# 12V_to_3V3.net
KiCad netlist of a schematic drawn in Altium Designer
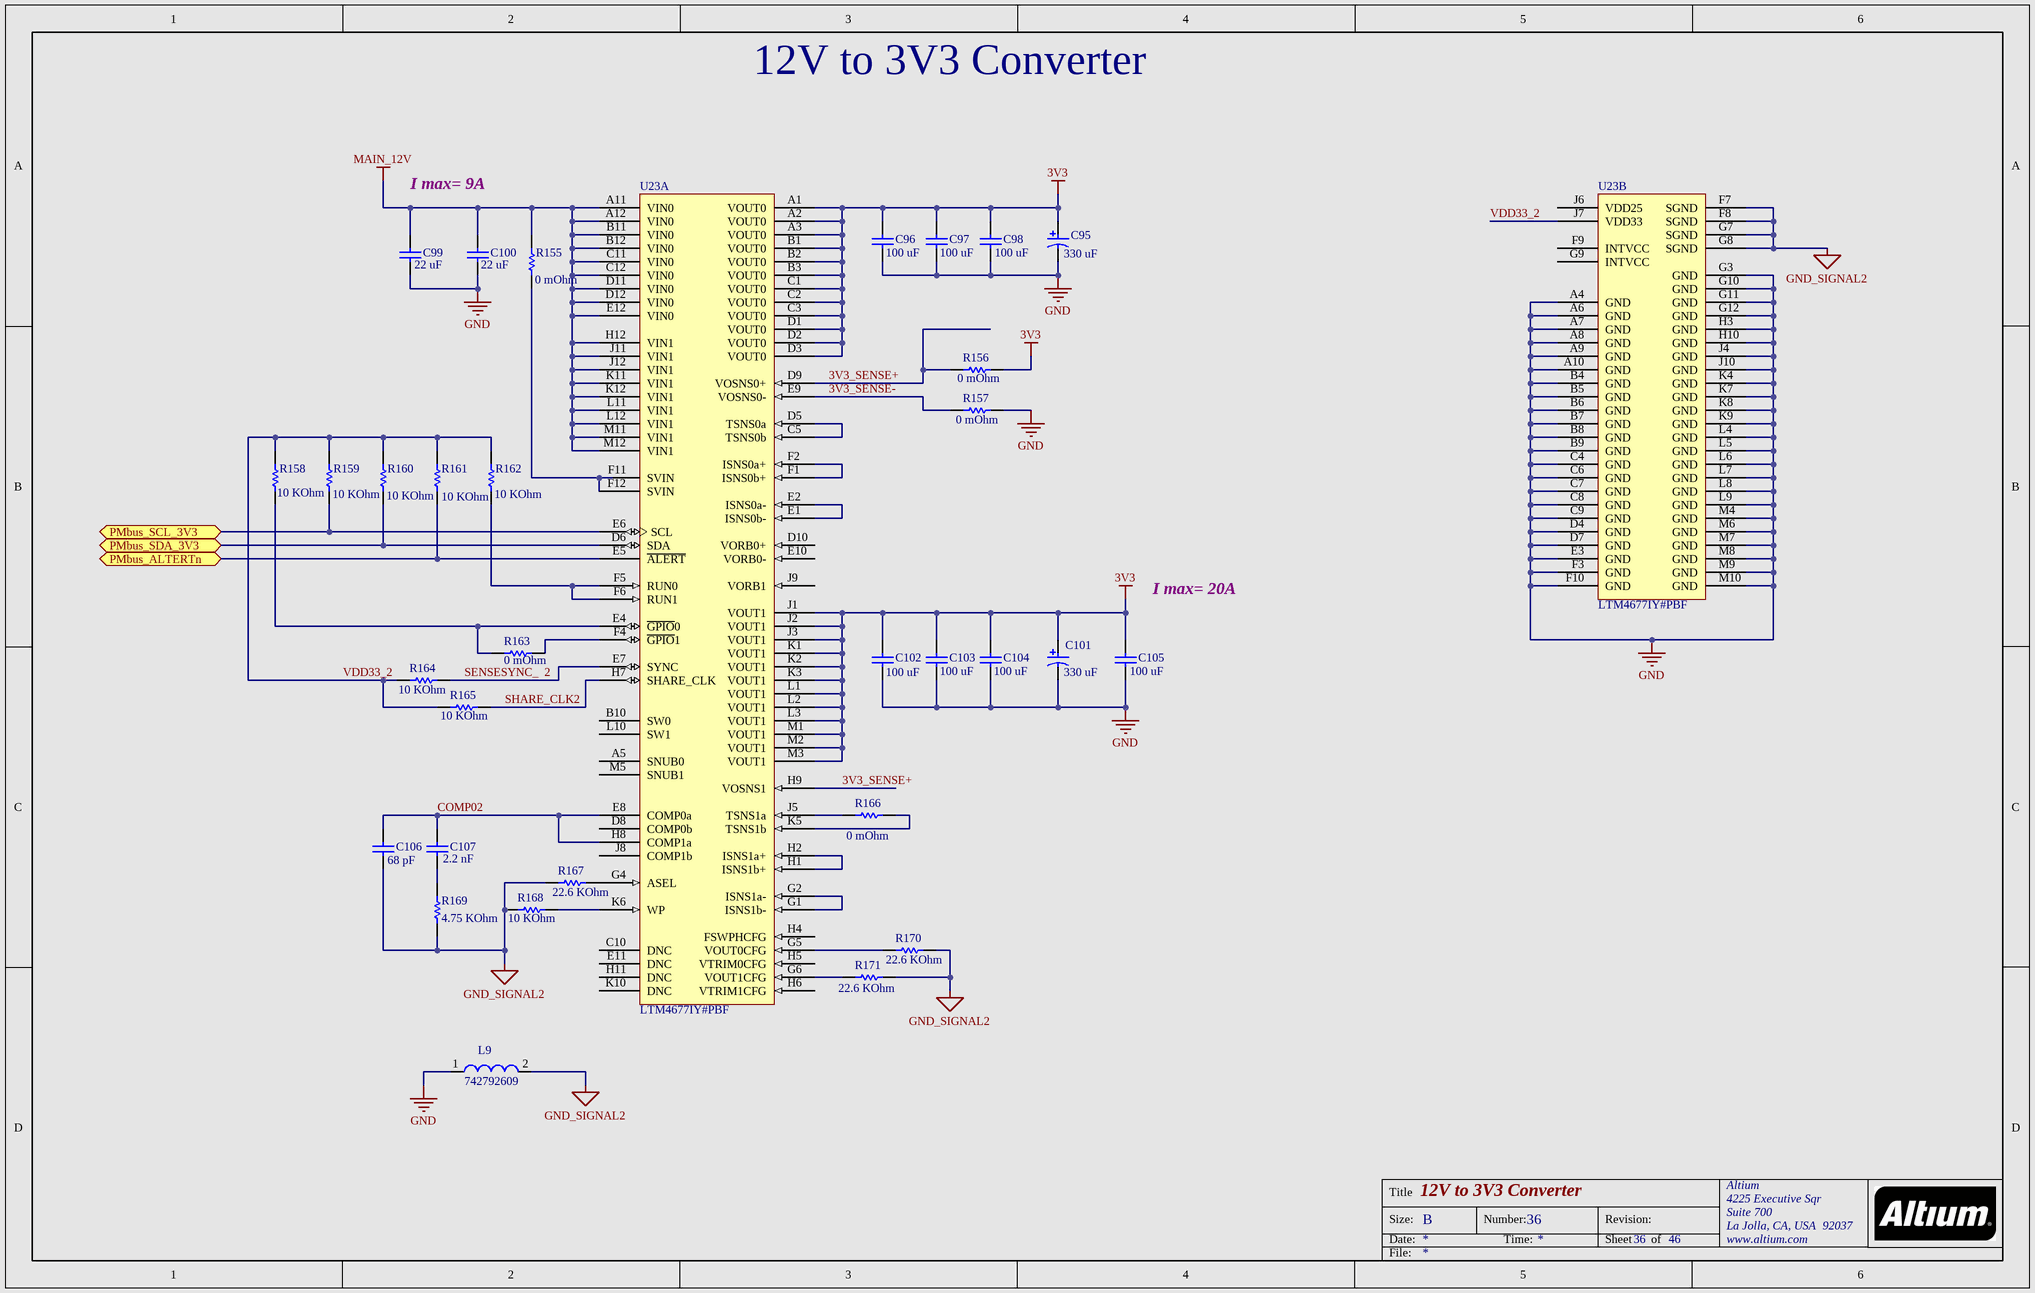
[diagram p0: 12V_to_3V3.SchDoc]

(export (version "E")
  (design (tool "Eeschema 10.0.6"))
  (components
    (comp (ref "C95")
      (value "6TPF330M9L")
      (footprint "PNSC-TPF-D3L_V")
      (description "Tantalum Capacitor, 330 uF, +/- 20%, 6.3 V, -55 to 105 degC, 2-Pin Molded, RoHS, Tape and Reel")
      (fields (field (name "CAPACITANCE") "330 uF"))
      (libsource (lib "Altium Content Vault") (part "CMP-1665-00019-2"))
    )
    (comp (ref "C96")
      (value "GRM31CR60J107ME39L")
      (footprint "CAPC3216X190X55ML30T25")
      (description "Chip Capacitor, 100 uF, +/- 20%, 6.3 V, -55 to 85 degC, 1206 (3216 Metric), RoHS, Tape and Reel")
      (fields (field (name "TOLERANCE") "20%") (field (name "CAPACITANCE") "100 uF"))
      (libsource (lib "Altium Content Vault") (part "CAP-NP-2"))
    )
    (comp (ref "C97")
      (value "GRM31CR60J107ME39L")
      (footprint "CAPC3216X190X55ML30T25")
      (description "Chip Capacitor, 100 uF, +/- 20%, 6.3 V, -55 to 85 degC, 1206 (3216 Metric), RoHS, Tape and Reel")
      (fields (field (name "TOLERANCE") "20%") (field (name "CAPACITANCE") "100 uF"))
      (libsource (lib "Altium Content Vault") (part "CAP-NP-2"))
    )
    (comp (ref "C98")
      (value "GRM31CR60J107ME39L")
      (footprint "CAPC3216X190X55ML30T25")
      (description "Chip Capacitor, 100 uF, +/- 20%, 6.3 V, -55 to 85 degC, 1206 (3216 Metric), RoHS, Tape and Reel")
      (fields (field (name "TOLERANCE") "20%") (field (name "CAPACITANCE") "100 uF"))
      (libsource (lib "Altium Content Vault") (part "CAP-NP-2"))
    )
    (comp (ref "C99")
      (value "GRM31CR61E226KE15L")
      (footprint "CAPC3216X180X55ML20T25")
      (description "Chip Capacitor, 22 uF, +/- 10%, 25 V, -55 to 85 degC, 1206 (3216 Metric), RoHS, Tape and Reel")
      (fields (field (name "TOLERANCE") "10%") (field (name "CAPACITANCE") "22 uF"))
      (libsource (lib "Altium Content Vault") (part "CAP-NP-2"))
    )
    (comp (ref "C100")
      (value "GRM31CR61E226KE15L")
      (footprint "CAPC3216X180X55ML20T25")
      (description "Chip Capacitor, 22 uF, +/- 10%, 25 V, -55 to 85 degC, 1206 (3216 Metric), RoHS, Tape and Reel")
      (fields (field (name "TOLERANCE") "10%") (field (name "CAPACITANCE") "22 uF"))
      (libsource (lib "Altium Content Vault") (part "CAP-NP-2"))
    )
    (comp (ref "C101")
      (value "6TPF330M9L")
      (footprint "PNSC-TPF-D3L_V")
      (description "Tantalum Capacitor, 330 uF, +/- 20%, 6.3 V, -55 to 105 degC, 2-Pin Molded, RoHS, Tape and Reel")
      (fields (field (name "CAPACITANCE") "330 uF"))
      (libsource (lib "Altium Content Vault") (part "CMP-1665-00019-2"))
    )
    (comp (ref "C102")
      (value "GRM31CR60J107ME39L")
      (footprint "CAPC3216X190X55ML30T25")
      (description "Chip Capacitor, 100 uF, +/- 20%, 6.3 V, -55 to 85 degC, 1206 (3216 Metric), RoHS, Tape and Reel")
      (fields (field (name "TOLERANCE") "20%") (field (name "CAPACITANCE") "100 uF"))
      (libsource (lib "Altium Content Vault") (part "CAP-NP-2"))
    )
    (comp (ref "C103")
      (value "GRM31CR60J107ME39L")
      (footprint "CAPC3216X190X55ML30T25")
      (description "Chip Capacitor, 100 uF, +/- 20%, 6.3 V, -55 to 85 degC, 1206 (3216 Metric), RoHS, Tape and Reel")
      (fields (field (name "TOLERANCE") "20%") (field (name "CAPACITANCE") "100 uF"))
      (libsource (lib "Altium Content Vault") (part "CAP-NP-2"))
    )
    (comp (ref "C104")
      (value "GRM31CR60J107ME39L")
      (footprint "CAPC3216X190X55ML30T25")
      (description "Chip Capacitor, 100 uF, +/- 20%, 6.3 V, -55 to 85 degC, 1206 (3216 Metric), RoHS, Tape and Reel")
      (fields (field (name "TOLERANCE") "20%") (field (name "CAPACITANCE") "100 uF"))
      (libsource (lib "Altium Content Vault") (part "CAP-NP-2"))
    )
    (comp (ref "C105")
      (value "GRM31CR60J107ME39L")
      (footprint "CAPC3216X190X55ML30T25")
      (description "Chip Capacitor, 100 uF, +/- 20%, 6.3 V, -55 to 85 degC, 1206 (3216 Metric), RoHS, Tape and Reel")
      (fields (field (name "TOLERANCE") "20%") (field (name "CAPACITANCE") "100 uF"))
      (libsource (lib "Altium Content Vault") (part "CAP-NP-2"))
    )
    (comp (ref "C106")
      (value "ECJ-0EC1H680J")
      (footprint "CAPC1005X55X20ML5T10")
      (description "Chip Capacitor, 68 pF, +/- 5%, 50 V, -55 to 125 degC, 0402 (1005 Metric), RoHS, Tape and Reel")
      (fields (field (name "TOLERANCE") "5%") (field (name "CAPACITANCE") "68 pF"))
      (libsource (lib "Altium Content Vault") (part "CMP-1665-00023-1"))
    )
    (comp (ref "C107")
      (value "CGJ2B2X7R1E222K050BA")
      (footprint "CAPC1005X55X10ML05")
      (description "Chip Capacitor, 2.2 nF, +/- 10%, 25 V, -55 to 125 degC, 0402 (1005 Metric), RoHS, Tape and Reel")
      (fields (field (name "TOLERANCE") "10%") (field (name "CAPACITANCE") "2.2 nF"))
      (libsource (lib "Altium Content Vault") (part "CAP-NP-2"))
    )
    (comp (ref "L9")
      (value "742792609")
      (footprint "SMD-0603")
      (description "SMD EMI Suppression Ferrite Bead WE-CBF, Z = 30 Ohm")
      (libsource (lib "Altium Content Vault") (part "CMP-0220-00193-1"))
    )
    (comp (ref "R155")
      (value "ERJ-2GE0R00X")
      (footprint "RESC1005X40X25ML05T05")
      (description "Chip Resistor, 0 mOhm, +/- 5%, 100 mW, -55 to 155 degC, 0402 (1005 Metric), RoHS, Tape and Reel")
      (fields
        (field (name "TOLERANCE") "5%")
        (field (name "RESISTANCE") "0 mOhm")
        (field (name "MANUFACTURER") "Basic Passives")
      )
      (libsource (lib "Altium Content Vault") (part "RES-2"))
    )
    (comp (ref "R156")
      (value "ERJ-2GE0R00X")
      (footprint "RESC1005X40X25ML05T05")
      (description "Chip Resistor, 0 mOhm, +/- 5%, 100 mW, -55 to 155 degC, 0402 (1005 Metric), RoHS, Tape and Reel")
      (fields
        (field (name "TOLERANCE") "5%")
        (field (name "RESISTANCE") "0 mOhm")
        (field (name "MANUFACTURER") "Basic Passives")
      )
      (libsource (lib "Altium Content Vault") (part "RES-2"))
    )
    (comp (ref "R157")
      (value "ERJ-2GE0R00X")
      (footprint "RESC1005X40X25ML05T05")
      (description "Chip Resistor, 0 mOhm, +/- 5%, 100 mW, -55 to 155 degC, 0402 (1005 Metric), RoHS, Tape and Reel")
      (fields
        (field (name "TOLERANCE") "5%")
        (field (name "RESISTANCE") "0 mOhm")
        (field (name "MANUFACTURER") "Basic Passives")
      )
      (libsource (lib "Altium Content Vault") (part "RES-2"))
    )
    (comp (ref "R158")
      (value "ERJ-2RKF1002X")
      (footprint "RESC1005X40X25NL05T05")
      (description "Chip Resistor, 10 KOhm, +/- 1%, 100 mW, -55 to 155 degC, 0402 (1005 Metric), RoHS, Tape and Reel")
      (fields
        (field (name "TOLERANCE") "1%")
        (field (name "RESISTANCE") "10 KOhm")
        (field (name "MANUFACTURER") "Basic Passives")
      )
      (libsource (lib "Altium Content Vault") (part "RES-2"))
    )
    (comp (ref "R159")
      (value "ERJ-2RKF1002X")
      (footprint "RESC1005X40X25NL05T05")
      (description "Chip Resistor, 10 KOhm, +/- 1%, 100 mW, -55 to 155 degC, 0402 (1005 Metric), RoHS, Tape and Reel")
      (fields
        (field (name "TOLERANCE") "1%")
        (field (name "RESISTANCE") "10 KOhm")
        (field (name "MANUFACTURER") "Basic Passives")
      )
      (libsource (lib "Altium Content Vault") (part "RES-2"))
    )
    (comp (ref "R160")
      (value "ERJ-2RKF1002X")
      (footprint "RESC1005X40X25NL05T05")
      (description "Chip Resistor, 10 KOhm, +/- 1%, 100 mW, -55 to 155 degC, 0402 (1005 Metric), RoHS, Tape and Reel")
      (fields
        (field (name "TOLERANCE") "1%")
        (field (name "RESISTANCE") "10 KOhm")
        (field (name "MANUFACTURER") "Basic Passives")
      )
      (libsource (lib "Altium Content Vault") (part "RES-2"))
    )
    (comp (ref "R161")
      (value "ERJ-2RKF1002X")
      (footprint "RESC1005X40X25NL05T05")
      (description "Chip Resistor, 10 KOhm, +/- 1%, 100 mW, -55 to 155 degC, 0402 (1005 Metric), RoHS, Tape and Reel")
      (fields
        (field (name "TOLERANCE") "1%")
        (field (name "RESISTANCE") "10 KOhm")
        (field (name "MANUFACTURER") "Basic Passives")
      )
      (libsource (lib "Altium Content Vault") (part "RES-2"))
    )
    (comp (ref "R162")
      (value "ERJ-2RKF1002X")
      (footprint "RESC1005X40X25NL05T05")
      (description "Chip Resistor, 10 KOhm, +/- 1%, 100 mW, -55 to 155 degC, 0402 (1005 Metric), RoHS, Tape and Reel")
      (fields
        (field (name "TOLERANCE") "1%")
        (field (name "RESISTANCE") "10 KOhm")
        (field (name "MANUFACTURER") "Basic Passives")
      )
      (libsource (lib "Altium Content Vault") (part "RES-2"))
    )
    (comp (ref "R163")
      (value "ERJ-2GE0R00X")
      (footprint "RESC1005X40X25ML05T05")
      (description "Chip Resistor, 0 mOhm, +/- 5%, 100 mW, -55 to 155 degC, 0402 (1005 Metric), RoHS, Tape and Reel")
      (fields
        (field (name "TOLERANCE") "5%")
        (field (name "RESISTANCE") "0 mOhm")
        (field (name "MANUFACTURER") "Basic Passives")
      )
      (libsource (lib "Altium Content Vault") (part "RES-2"))
    )
    (comp (ref "R164")
      (value "ERJ-2RKF1002X")
      (footprint "RESC1005X40X25NL05T05")
      (description "Chip Resistor, 10 KOhm, +/- 1%, 100 mW, -55 to 155 degC, 0402 (1005 Metric), RoHS, Tape and Reel")
      (fields
        (field (name "TOLERANCE") "1%")
        (field (name "RESISTANCE") "10 KOhm")
        (field (name "MANUFACTURER") "Basic Passives")
      )
      (libsource (lib "Altium Content Vault") (part "RES-2"))
    )
    (comp (ref "R165")
      (value "ERJ-2RKF1002X")
      (footprint "RESC1005X40X25NL05T05")
      (description "Chip Resistor, 10 KOhm, +/- 1%, 100 mW, -55 to 155 degC, 0402 (1005 Metric), RoHS, Tape and Reel")
      (fields
        (field (name "TOLERANCE") "1%")
        (field (name "RESISTANCE") "10 KOhm")
        (field (name "MANUFACTURER") "Basic Passives")
      )
      (libsource (lib "Altium Content Vault") (part "RES-2"))
    )
    (comp (ref "R166")
      (value "ERJ-2GE0R00X")
      (footprint "RESC1005X40X25ML05T05")
      (description "Chip Resistor, 0 mOhm, +/- 5%, 100 mW, -55 to 155 degC, 0402 (1005 Metric), RoHS, Tape and Reel")
      (fields
        (field (name "TOLERANCE") "5%")
        (field (name "RESISTANCE") "0 mOhm")
        (field (name "MANUFACTURER") "Basic Passives")
      )
      (libsource (lib "Altium Content Vault") (part "RES-2"))
    )
    (comp (ref "R167")
      (value "CRCW040222K6FKED")
      (footprint "RESC1005X40X25LL05T05")
      (description "Chip Resistor, 22.6 KOhm, +/- 1%, 63 mW, -55 to 155 degC, 0402 (1005 Metric), RoHS, Tape and Reel")
      (fields (field (name "RESISTANCE") "22.6 KOhm") (field (name "TOLERANCE") "1%"))
      (libsource (lib "Altium Content Vault") (part "RES"))
    )
    (comp (ref "R168")
      (value "ERJ-2RKF1002X")
      (footprint "RESC1005X40X25NL05T05")
      (description "Chip Resistor, 10 KOhm, +/- 1%, 100 mW, -55 to 155 degC, 0402 (1005 Metric), RoHS, Tape and Reel")
      (fields
        (field (name "TOLERANCE") "1%")
        (field (name "RESISTANCE") "10 KOhm")
        (field (name "MANUFACTURER") "Basic Passives")
      )
      (libsource (lib "Altium Content Vault") (part "RES-2"))
    )
    (comp (ref "R169")
      (value "ERJ-2RKF4751X")
      (footprint "RESC1005X40X25ML05T05")
      (description "Chip Resistor, 4.75 KOhm, +/- 1%, 100 mW, -55 to 155 degC, 0402 (1005 Metric), RoHS, Tape and Reel")
      (fields
        (field (name "RESISTANCE") "4.75 KOhm")
        (field (name "TOLERANCE") "1%")
        (field (name "MANUFACTURER") "Basic Passives")
      )
      (libsource (lib "Altium Content Vault") (part "RES-2"))
    )
    (comp (ref "R170")
      (value "CRCW040222K6FKED")
      (footprint "RESC1005X40X25LL05T05")
      (description "Chip Resistor, 22.6 KOhm, +/- 1%, 63 mW, -55 to 155 degC, 0402 (1005 Metric), RoHS, Tape and Reel")
      (fields (field (name "RESISTANCE") "22.6 KOhm") (field (name "TOLERANCE") "1%"))
      (libsource (lib "Altium Content Vault") (part "RES"))
    )
    (comp (ref "R171")
      (value "CRCW040222K6FKED")
      (footprint "RESC1005X40X25LL05T05")
      (description "Chip Resistor, 22.6 KOhm, +/- 1%, 63 mW, -55 to 155 degC, 0402 (1005 Metric), RoHS, Tape and Reel")
      (fields (field (name "RESISTANCE") "22.6 KOhm") (field (name "TOLERANCE") "1%"))
      (libsource (lib "Altium Content Vault") (part "RES"))
    )
    (comp (ref "U23")
      (value "LTM4677IY#PBF")
      (footprint "LT-BGA-144-05-08-1920_V")
      (fields (field (name "MANUFACTURER") "Linear Technology"))
      (libsource (lib "Altium Content Vault") (part "CMP-1701-00001-1"))
    )
  )
  (nets
    (net (code "1") (name "/3V3_SENSE+") (class "Default")
      (node (ref "R156") (pin "1") (pinfunction "1_1") (pintype "passive"))
      (node (ref "U23") (pin "D9") (pinfunction "VOSNS0+_D9") (pintype "input"))
      (node (ref "U23") (pin "H9") (pinfunction "VOSNS1_H9") (pintype "input"))
    )
    (net (code "2") (name "/3V3_SENSE-") (class "Default")
      (node (ref "R157") (pin "1") (pinfunction "1_1") (pintype "passive"))
      (node (ref "U23") (pin "E9") (pinfunction "VOSNS0-_E9") (pintype "input"))
    )
    (net (code "3") (name "/COMP02") (class "Default")
      (node (ref "C106") (pin "2") (pinfunction "2_2") (pintype "passive"))
      (node (ref "C107") (pin "2") (pinfunction "2_2") (pintype "passive"))
      (node (ref "U23") (pin "E8") (pinfunction "COMP0a_E8") (pintype "passive"))
      (node (ref "U23") (pin "H8") (pinfunction "COMP1a_H8") (pintype "passive"))
    )
    (net (code "4") (name "/PMbus_ALTERTn") (class "Default")
      (node (ref "R161") (pin "1") (pinfunction "1_1") (pintype "passive"))
      (node (ref "U23") (pin "E5") (pinfunction "~{ALERT}_E5") (pintype "open_collector"))
    )
    (net (code "5") (name "/PMbus_SCL_3V3") (class "Default")
      (node (ref "R159") (pin "1") (pinfunction "1_1") (pintype "passive"))
      (node (ref "U23") (pin "E6") (pinfunction "SCL_E6") (pintype "bidirectional"))
    )
    (net (code "6") (name "/PMbus_SDA_3V3") (class "Default")
      (node (ref "R160") (pin "1") (pinfunction "1_1") (pintype "passive"))
      (node (ref "U23") (pin "D6") (pinfunction "SDA_D6") (pintype "bidirectional"))
    )
    (net (code "7") (name "/SENSESYNC_  2") (class "Default")
      (node (ref "R164") (pin "1") (pinfunction "1_1") (pintype "passive"))
      (node (ref "U23") (pin "E7") (pinfunction "SYNC_E7") (pintype "bidirectional"))
    )
    (net (code "8") (name "/SHARE_CLK2") (class "Default")
      (node (ref "R165") (pin "1") (pinfunction "1_1") (pintype "passive"))
      (node (ref "U23") (pin "H7") (pinfunction "SHARE_CLK_H7") (pintype "bidirectional"))
    )
    (net (code "9") (name "/VDD33_2") (class "Default")
      (node (ref "R158") (pin "2") (pinfunction "2_2") (pintype "passive"))
      (node (ref "R159") (pin "2") (pinfunction "2_2") (pintype "passive"))
      (node (ref "R160") (pin "2") (pinfunction "2_2") (pintype "passive"))
      (node (ref "R161") (pin "2") (pinfunction "2_2") (pintype "passive"))
      (node (ref "R162") (pin "2") (pinfunction "2_2") (pintype "passive"))
      (node (ref "R164") (pin "2") (pinfunction "2_2") (pintype "passive"))
      (node (ref "R165") (pin "2") (pinfunction "2_2") (pintype "passive"))
      (node (ref "U23") (pin "J7") (pinfunction "VDD33_J7") (pintype "power_in"))
    )
    (net (code "10") (name "3V3") (class "Default")
      (node (ref "C101") (pin "1") (pinfunction "1_1") (pintype "passive"))
      (node (ref "C102") (pin "2") (pinfunction "2_2") (pintype "passive"))
      (node (ref "C103") (pin "2") (pinfunction "2_2") (pintype "passive"))
      (node (ref "C104") (pin "2") (pinfunction "2_2") (pintype "passive"))
      (node (ref "C105") (pin "2") (pinfunction "2_2") (pintype "passive"))
      (node (ref "C95") (pin "1") (pinfunction "1_1") (pintype "passive"))
      (node (ref "C96") (pin "2") (pinfunction "2_2") (pintype "passive"))
      (node (ref "C97") (pin "2") (pinfunction "2_2") (pintype "passive"))
      (node (ref "C98") (pin "2") (pinfunction "2_2") (pintype "passive"))
      (node (ref "R156") (pin "2") (pinfunction "2_2") (pintype "passive"))
      (node (ref "U23") (pin "A1") (pinfunction "VOUT0_A1") (pintype "power_in"))
      (node (ref "U23") (pin "A2") (pinfunction "VOUT0_A2") (pintype "power_in"))
      (node (ref "U23") (pin "A3") (pinfunction "VOUT0_A3") (pintype "power_in"))
      (node (ref "U23") (pin "B1") (pinfunction "VOUT0_B1") (pintype "power_in"))
      (node (ref "U23") (pin "B2") (pinfunction "VOUT0_B2") (pintype "power_in"))
      (node (ref "U23") (pin "B3") (pinfunction "VOUT0_B3") (pintype "power_in"))
      (node (ref "U23") (pin "C1") (pinfunction "VOUT0_C1") (pintype "power_in"))
      (node (ref "U23") (pin "C2") (pinfunction "VOUT0_C2") (pintype "power_in"))
      (node (ref "U23") (pin "C3") (pinfunction "VOUT0_C3") (pintype "power_in"))
      (node (ref "U23") (pin "D1") (pinfunction "VOUT0_D1") (pintype "power_in"))
      (node (ref "U23") (pin "D2") (pinfunction "VOUT0_D2") (pintype "power_in"))
      (node (ref "U23") (pin "D3") (pinfunction "VOUT0_D3") (pintype "power_in"))
      (node (ref "U23") (pin "J1") (pinfunction "VOUT1_J1") (pintype "power_in"))
      (node (ref "U23") (pin "J2") (pinfunction "VOUT1_J2") (pintype "power_in"))
      (node (ref "U23") (pin "J3") (pinfunction "VOUT1_J3") (pintype "power_in"))
      (node (ref "U23") (pin "K1") (pinfunction "VOUT1_K1") (pintype "power_in"))
      (node (ref "U23") (pin "K2") (pinfunction "VOUT1_K2") (pintype "power_in"))
      (node (ref "U23") (pin "K3") (pinfunction "VOUT1_K3") (pintype "power_in"))
      (node (ref "U23") (pin "L1") (pinfunction "VOUT1_L1") (pintype "power_in"))
      (node (ref "U23") (pin "L2") (pinfunction "VOUT1_L2") (pintype "power_in"))
      (node (ref "U23") (pin "L3") (pinfunction "VOUT1_L3") (pintype "power_in"))
      (node (ref "U23") (pin "M1") (pinfunction "VOUT1_M1") (pintype "power_in"))
      (node (ref "U23") (pin "M2") (pinfunction "VOUT1_M2") (pintype "power_in"))
      (node (ref "U23") (pin "M3") (pinfunction "VOUT1_M3") (pintype "power_in"))
    )
    (net (code "11") (name "GND") (class "Default")
      (node (ref "C100") (pin "1") (pinfunction "1_1") (pintype "passive"))
      (node (ref "C101") (pin "2") (pinfunction "2_2") (pintype "passive"))
      (node (ref "C102") (pin "1") (pinfunction "1_1") (pintype "passive"))
      (node (ref "C103") (pin "1") (pinfunction "1_1") (pintype "passive"))
      (node (ref "C104") (pin "1") (pinfunction "1_1") (pintype "passive"))
      (node (ref "C105") (pin "1") (pinfunction "1_1") (pintype "passive"))
      (node (ref "C95") (pin "2") (pinfunction "2_2") (pintype "passive"))
      (node (ref "C96") (pin "1") (pinfunction "1_1") (pintype "passive"))
      (node (ref "C97") (pin "1") (pinfunction "1_1") (pintype "passive"))
      (node (ref "C98") (pin "1") (pinfunction "1_1") (pintype "passive"))
      (node (ref "C99") (pin "1") (pinfunction "1_1") (pintype "passive"))
      (node (ref "L9") (pin "1") (pinfunction "1_1") (pintype "passive"))
      (node (ref "R157") (pin "2") (pinfunction "2_2") (pintype "passive"))
      (node (ref "U23") (pin "A10") (pinfunction "GND_A10") (pintype "power_in"))
      (node (ref "U23") (pin "A4") (pinfunction "GND_A4") (pintype "power_in"))
      (node (ref "U23") (pin "A6") (pinfunction "GND_A6") (pintype "power_in"))
      (node (ref "U23") (pin "A7") (pinfunction "GND_A7") (pintype "power_in"))
      (node (ref "U23") (pin "A8") (pinfunction "GND_A8") (pintype "power_in"))
      (node (ref "U23") (pin "A9") (pinfunction "GND_A9") (pintype "power_in"))
      (node (ref "U23") (pin "B4") (pinfunction "GND_B4") (pintype "power_in"))
      (node (ref "U23") (pin "B5") (pinfunction "GND_B5") (pintype "power_in"))
      (node (ref "U23") (pin "B6") (pinfunction "GND_B6") (pintype "power_in"))
      (node (ref "U23") (pin "B7") (pinfunction "GND_B7") (pintype "power_in"))
      (node (ref "U23") (pin "B8") (pinfunction "GND_B8") (pintype "power_in"))
      (node (ref "U23") (pin "B9") (pinfunction "GND_B9") (pintype "power_in"))
      (node (ref "U23") (pin "C4") (pinfunction "GND_C4") (pintype "power_in"))
      (node (ref "U23") (pin "C6") (pinfunction "GND_C6") (pintype "power_in"))
      (node (ref "U23") (pin "C7") (pinfunction "GND_C7") (pintype "power_in"))
      (node (ref "U23") (pin "C8") (pinfunction "GND_C8") (pintype "power_in"))
      (node (ref "U23") (pin "C9") (pinfunction "GND_C9") (pintype "power_in"))
      (node (ref "U23") (pin "D4") (pinfunction "GND_D4") (pintype "power_in"))
      (node (ref "U23") (pin "D7") (pinfunction "GND_D7") (pintype "power_in"))
      (node (ref "U23") (pin "E3") (pinfunction "GND_E3") (pintype "power_in"))
      (node (ref "U23") (pin "F10") (pinfunction "GND_F10") (pintype "power_in"))
      (node (ref "U23") (pin "F3") (pinfunction "GND_F3") (pintype "power_in"))
      (node (ref "U23") (pin "G10") (pinfunction "GND_G10") (pintype "power_in"))
      (node (ref "U23") (pin "G11") (pinfunction "GND_G11") (pintype "power_in"))
      (node (ref "U23") (pin "G12") (pinfunction "GND_G12") (pintype "power_in"))
      (node (ref "U23") (pin "G3") (pinfunction "GND_G3") (pintype "power_in"))
      (node (ref "U23") (pin "H10") (pinfunction "GND_H10") (pintype "power_in"))
      (node (ref "U23") (pin "H3") (pinfunction "GND_H3") (pintype "power_in"))
      (node (ref "U23") (pin "J10") (pinfunction "GND_J10") (pintype "power_in"))
      (node (ref "U23") (pin "J4") (pinfunction "GND_J4") (pintype "power_in"))
      (node (ref "U23") (pin "K4") (pinfunction "GND_K4") (pintype "power_in"))
      (node (ref "U23") (pin "K7") (pinfunction "GND_K7") (pintype "power_in"))
      (node (ref "U23") (pin "K8") (pinfunction "GND_K8") (pintype "power_in"))
      (node (ref "U23") (pin "K9") (pinfunction "GND_K9") (pintype "power_in"))
      (node (ref "U23") (pin "L4") (pinfunction "GND_L4") (pintype "power_in"))
      (node (ref "U23") (pin "L5") (pinfunction "GND_L5") (pintype "power_in"))
      (node (ref "U23") (pin "L6") (pinfunction "GND_L6") (pintype "power_in"))
      (node (ref "U23") (pin "L7") (pinfunction "GND_L7") (pintype "power_in"))
      (node (ref "U23") (pin "L8") (pinfunction "GND_L8") (pintype "power_in"))
      (node (ref "U23") (pin "L9") (pinfunction "GND_L9") (pintype "power_in"))
      (node (ref "U23") (pin "M10") (pinfunction "GND_M10") (pintype "power_in"))
      (node (ref "U23") (pin "M4") (pinfunction "GND_M4") (pintype "power_in"))
      (node (ref "U23") (pin "M6") (pinfunction "GND_M6") (pintype "power_in"))
      (node (ref "U23") (pin "M7") (pinfunction "GND_M7") (pintype "power_in"))
      (node (ref "U23") (pin "M8") (pinfunction "GND_M8") (pintype "power_in"))
      (node (ref "U23") (pin "M9") (pinfunction "GND_M9") (pintype "power_in"))
    )
    (net (code "12") (name "GND_SIGNAL2") (class "Default")
      (node (ref "C106") (pin "1") (pinfunction "1_1") (pintype "passive"))
      (node (ref "L9") (pin "2") (pinfunction "2_2") (pintype "passive"))
      (node (ref "R167") (pin "1") (pinfunction "1_1") (pintype "passive"))
      (node (ref "R168") (pin "2") (pinfunction "2_2") (pintype "passive"))
      (node (ref "R169") (pin "1") (pinfunction "1_1") (pintype "passive"))
      (node (ref "R170") (pin "2") (pinfunction "2_2") (pintype "passive"))
      (node (ref "R171") (pin "2") (pinfunction "2_2") (pintype "passive"))
      (node (ref "U23") (pin "F7") (pinfunction "SGND_F7") (pintype "power_in"))
      (node (ref "U23") (pin "F8") (pinfunction "SGND_F8") (pintype "power_in"))
      (node (ref "U23") (pin "G7") (pinfunction "SGND_G7") (pintype "power_in"))
      (node (ref "U23") (pin "G8") (pinfunction "SGND_G8") (pintype "power_in"))
    )
    (net (code "13") (name "MAIN_12V") (class "Default")
      (node (ref "C100") (pin "2") (pinfunction "2_2") (pintype "passive"))
      (node (ref "C99") (pin "2") (pinfunction "2_2") (pintype "passive"))
      (node (ref "R155") (pin "2") (pinfunction "2_2") (pintype "passive"))
      (node (ref "U23") (pin "A11") (pinfunction "VIN0_A11") (pintype "power_in"))
      (node (ref "U23") (pin "A12") (pinfunction "VIN0_A12") (pintype "power_in"))
      (node (ref "U23") (pin "B11") (pinfunction "VIN0_B11") (pintype "power_in"))
      (node (ref "U23") (pin "B12") (pinfunction "VIN0_B12") (pintype "power_in"))
      (node (ref "U23") (pin "C11") (pinfunction "VIN0_C11") (pintype "power_in"))
      (node (ref "U23") (pin "C12") (pinfunction "VIN0_C12") (pintype "power_in"))
      (node (ref "U23") (pin "D11") (pinfunction "VIN0_D11") (pintype "power_in"))
      (node (ref "U23") (pin "D12") (pinfunction "VIN0_D12") (pintype "power_in"))
      (node (ref "U23") (pin "E12") (pinfunction "VIN0_E12") (pintype "power_in"))
      (node (ref "U23") (pin "H12") (pinfunction "VIN1_H12") (pintype "power_in"))
      (node (ref "U23") (pin "J11") (pinfunction "VIN1_J11") (pintype "power_in"))
      (node (ref "U23") (pin "J12") (pinfunction "VIN1_J12") (pintype "power_in"))
      (node (ref "U23") (pin "K11") (pinfunction "VIN1_K11") (pintype "power_in"))
      (node (ref "U23") (pin "K12") (pinfunction "VIN1_K12") (pintype "power_in"))
      (node (ref "U23") (pin "L11") (pinfunction "VIN1_L11") (pintype "power_in"))
      (node (ref "U23") (pin "L12") (pinfunction "VIN1_L12") (pintype "power_in"))
      (node (ref "U23") (pin "M11") (pinfunction "VIN1_M11") (pintype "power_in"))
      (node (ref "U23") (pin "M12") (pinfunction "VIN1_M12") (pintype "power_in"))
    )
    (net (code "14") (name "Net-(C107-Pad1)") (class "Default")
      (node (ref "C107") (pin "1") (pinfunction "1_1") (pintype "passive"))
      (node (ref "R169") (pin "2") (pinfunction "2_2") (pintype "passive"))
    )
    (net (code "15") (name "Net-(R155-Pad1)") (class "Default")
      (node (ref "R155") (pin "1") (pinfunction "1_1") (pintype "passive"))
      (node (ref "U23") (pin "F11") (pinfunction "SVIN_F11") (pintype "power_in"))
      (node (ref "U23") (pin "F12") (pinfunction "SVIN_F12") (pintype "power_in"))
    )
    (net (code "16") (name "Net-(U23A-ASEL)") (class "Default")
      (node (ref "R167") (pin "2") (pinfunction "2_2") (pintype "passive"))
      (node (ref "U23") (pin "G4") (pinfunction "ASEL_G4") (pintype "input"))
    )
    (net (code "17") (name "Net-(U23A-ISNS0a+)") (class "Default")
      (node (ref "U23") (pin "F1") (pinfunction "ISNS0b+_F1") (pintype "input"))
      (node (ref "U23") (pin "F2") (pinfunction "ISNS0a+_F2") (pintype "input"))
    )
    (net (code "18") (name "Net-(U23A-ISNS0a-)") (class "Default")
      (node (ref "U23") (pin "E1") (pinfunction "ISNS0b-_E1") (pintype "input"))
      (node (ref "U23") (pin "E2") (pinfunction "ISNS0a-_E2") (pintype "input"))
    )
    (net (code "19") (name "Net-(U23A-ISNS1a+)") (class "Default")
      (node (ref "U23") (pin "H1") (pinfunction "ISNS1b+_H1") (pintype "input"))
      (node (ref "U23") (pin "H2") (pinfunction "ISNS1a+_H2") (pintype "input"))
    )
    (net (code "20") (name "Net-(U23A-ISNS1a-)") (class "Default")
      (node (ref "U23") (pin "G1") (pinfunction "ISNS1b-_G1") (pintype "input"))
      (node (ref "U23") (pin "G2") (pinfunction "ISNS1a-_G2") (pintype "input"))
    )
    (net (code "21") (name "Net-(U23A-RUN0)") (class "Default")
      (node (ref "R162") (pin "1") (pinfunction "1_1") (pintype "passive"))
      (node (ref "U23") (pin "F5") (pinfunction "RUN0_F5") (pintype "input"))
      (node (ref "U23") (pin "F6") (pinfunction "RUN1_F6") (pintype "input"))
    )
    (net (code "22") (name "Net-(U23A-TSNS0a)") (class "Default")
      (node (ref "U23") (pin "C5") (pinfunction "TSNS0b_C5") (pintype "input"))
      (node (ref "U23") (pin "D5") (pinfunction "TSNS0a_D5") (pintype "input"))
    )
    (net (code "23") (name "Net-(U23A-TSNS1a)") (class "Default")
      (node (ref "R166") (pin "1") (pinfunction "1_1") (pintype "passive"))
      (node (ref "U23") (pin "J5") (pinfunction "TSNS1a_J5") (pintype "input"))
    )
    (net (code "24") (name "Net-(U23A-TSNS1b)") (class "Default")
      (node (ref "R166") (pin "2") (pinfunction "2_2") (pintype "passive"))
      (node (ref "U23") (pin "K5") (pinfunction "TSNS1b_K5") (pintype "input"))
    )
    (net (code "25") (name "Net-(U23A-VOUT0CFG)") (class "Default")
      (node (ref "R170") (pin "1") (pinfunction "1_1") (pintype "passive"))
      (node (ref "U23") (pin "G5") (pinfunction "VOUT0CFG_G5") (pintype "input"))
    )
    (net (code "26") (name "Net-(U23A-VOUT1CFG)") (class "Default")
      (node (ref "R171") (pin "1") (pinfunction "1_1") (pintype "passive"))
      (node (ref "U23") (pin "G6") (pinfunction "VOUT1CFG_G6") (pintype "input"))
    )
    (net (code "27") (name "Net-(U23A-WP)") (class "Default")
      (node (ref "R168") (pin "1") (pinfunction "1_1") (pintype "passive"))
      (node (ref "U23") (pin "K6") (pinfunction "WP_K6") (pintype "input"))
    )
    (net (code "28") (name "Net-(U23A-~{GPIO}0)") (class "Default")
      (node (ref "R158") (pin "1") (pinfunction "1_1") (pintype "passive"))
      (node (ref "R163") (pin "2") (pinfunction "2_2") (pintype "passive"))
      (node (ref "U23") (pin "E4") (pinfunction "~{GPIO}0_E4") (pintype "bidirectional"))
    )
    (net (code "29") (name "Net-(U23A-~{GPIO}1)") (class "Default")
      (node (ref "R163") (pin "1") (pinfunction "1_1") (pintype "passive"))
      (node (ref "U23") (pin "F4") (pinfunction "~{GPIO}1_F4") (pintype "bidirectional"))
    )
    (net (code "30") (name "unconnected-(U23A-COMP0b-PadD8)") (class "Default")
      (node (ref "U23") (pin "D8") (pinfunction "COMP0b_D8") (pintype "passive"))
    )
    (net (code "31") (name "unconnected-(U23A-COMP1b-PadJ8)") (class "Default")
      (node (ref "U23") (pin "J8") (pinfunction "COMP1b_J8") (pintype "passive"))
    )
    (net (code "32") (name "unconnected-(U23A-DNC-PadC10)") (class "Default")
      (node (ref "U23") (pin "C10") (pinfunction "DNC_C10") (pintype "passive"))
    )
    (net (code "33") (name "unconnected-(U23A-DNC-PadE11)") (class "Default")
      (node (ref "U23") (pin "E11") (pinfunction "DNC_E11") (pintype "passive"))
    )
    (net (code "34") (name "unconnected-(U23A-DNC-PadH11)") (class "Default")
      (node (ref "U23") (pin "H11") (pinfunction "DNC_H11") (pintype "passive"))
    )
    (net (code "35") (name "unconnected-(U23A-DNC-PadK10)") (class "Default")
      (node (ref "U23") (pin "K10") (pinfunction "DNC_K10") (pintype "passive"))
    )
    (net (code "36") (name "unconnected-(U23A-FSWPHCFG-PadH4)") (class "Default")
      (node (ref "U23") (pin "H4") (pinfunction "FSWPHCFG_H4") (pintype "input"))
    )
    (net (code "37") (name "unconnected-(U23A-SNUB0-PadA5)") (class "Default")
      (node (ref "U23") (pin "A5") (pinfunction "SNUB0_A5") (pintype "passive"))
    )
    (net (code "38") (name "unconnected-(U23A-SNUB1-PadM5)") (class "Default")
      (node (ref "U23") (pin "M5") (pinfunction "SNUB1_M5") (pintype "passive"))
    )
    (net (code "39") (name "unconnected-(U23A-SW0-PadB10)") (class "Default")
      (node (ref "U23") (pin "B10") (pinfunction "SW0_B10") (pintype "passive"))
    )
    (net (code "40") (name "unconnected-(U23A-SW1-PadL10)") (class "Default")
      (node (ref "U23") (pin "L10") (pinfunction "SW1_L10") (pintype "passive"))
    )
    (net (code "41") (name "unconnected-(U23A-VORB0+-PadD10)") (class "Default")
      (node (ref "U23") (pin "D10") (pinfunction "VORB0+_D10") (pintype "input"))
    )
    (net (code "42") (name "unconnected-(U23A-VORB0--PadE10)") (class "Default")
      (node (ref "U23") (pin "E10") (pinfunction "VORB0-_E10") (pintype "input"))
    )
    (net (code "43") (name "unconnected-(U23A-VORB1-PadJ9)") (class "Default")
      (node (ref "U23") (pin "J9") (pinfunction "VORB1_J9") (pintype "input"))
    )
    (net (code "44") (name "unconnected-(U23A-VTRIM0CFG-PadH5)") (class "Default")
      (node (ref "U23") (pin "H5") (pinfunction "VTRIM0CFG_H5") (pintype "input"))
    )
    (net (code "45") (name "unconnected-(U23A-VTRIM1CFG-PadH6)") (class "Default")
      (node (ref "U23") (pin "H6") (pinfunction "VTRIM1CFG_H6") (pintype "input"))
    )
    (net (code "46") (name "unconnected-(U23B-INTVCC-PadF9)") (class "Default")
      (node (ref "U23") (pin "F9") (pinfunction "INTVCC_F9") (pintype "power_in"))
    )
    (net (code "47") (name "unconnected-(U23B-INTVCC-PadG9)") (class "Default")
      (node (ref "U23") (pin "G9") (pinfunction "INTVCC_G9") (pintype "power_in"))
    )
    (net (code "48") (name "unconnected-(U23B-VDD25-PadJ6)") (class "Default")
      (node (ref "U23") (pin "J6") (pinfunction "VDD25_J6") (pintype "power_in"))
    )
  )
)
